# legatus_1_1.net
KiCad netlist of a schematic drawn in EAGLE
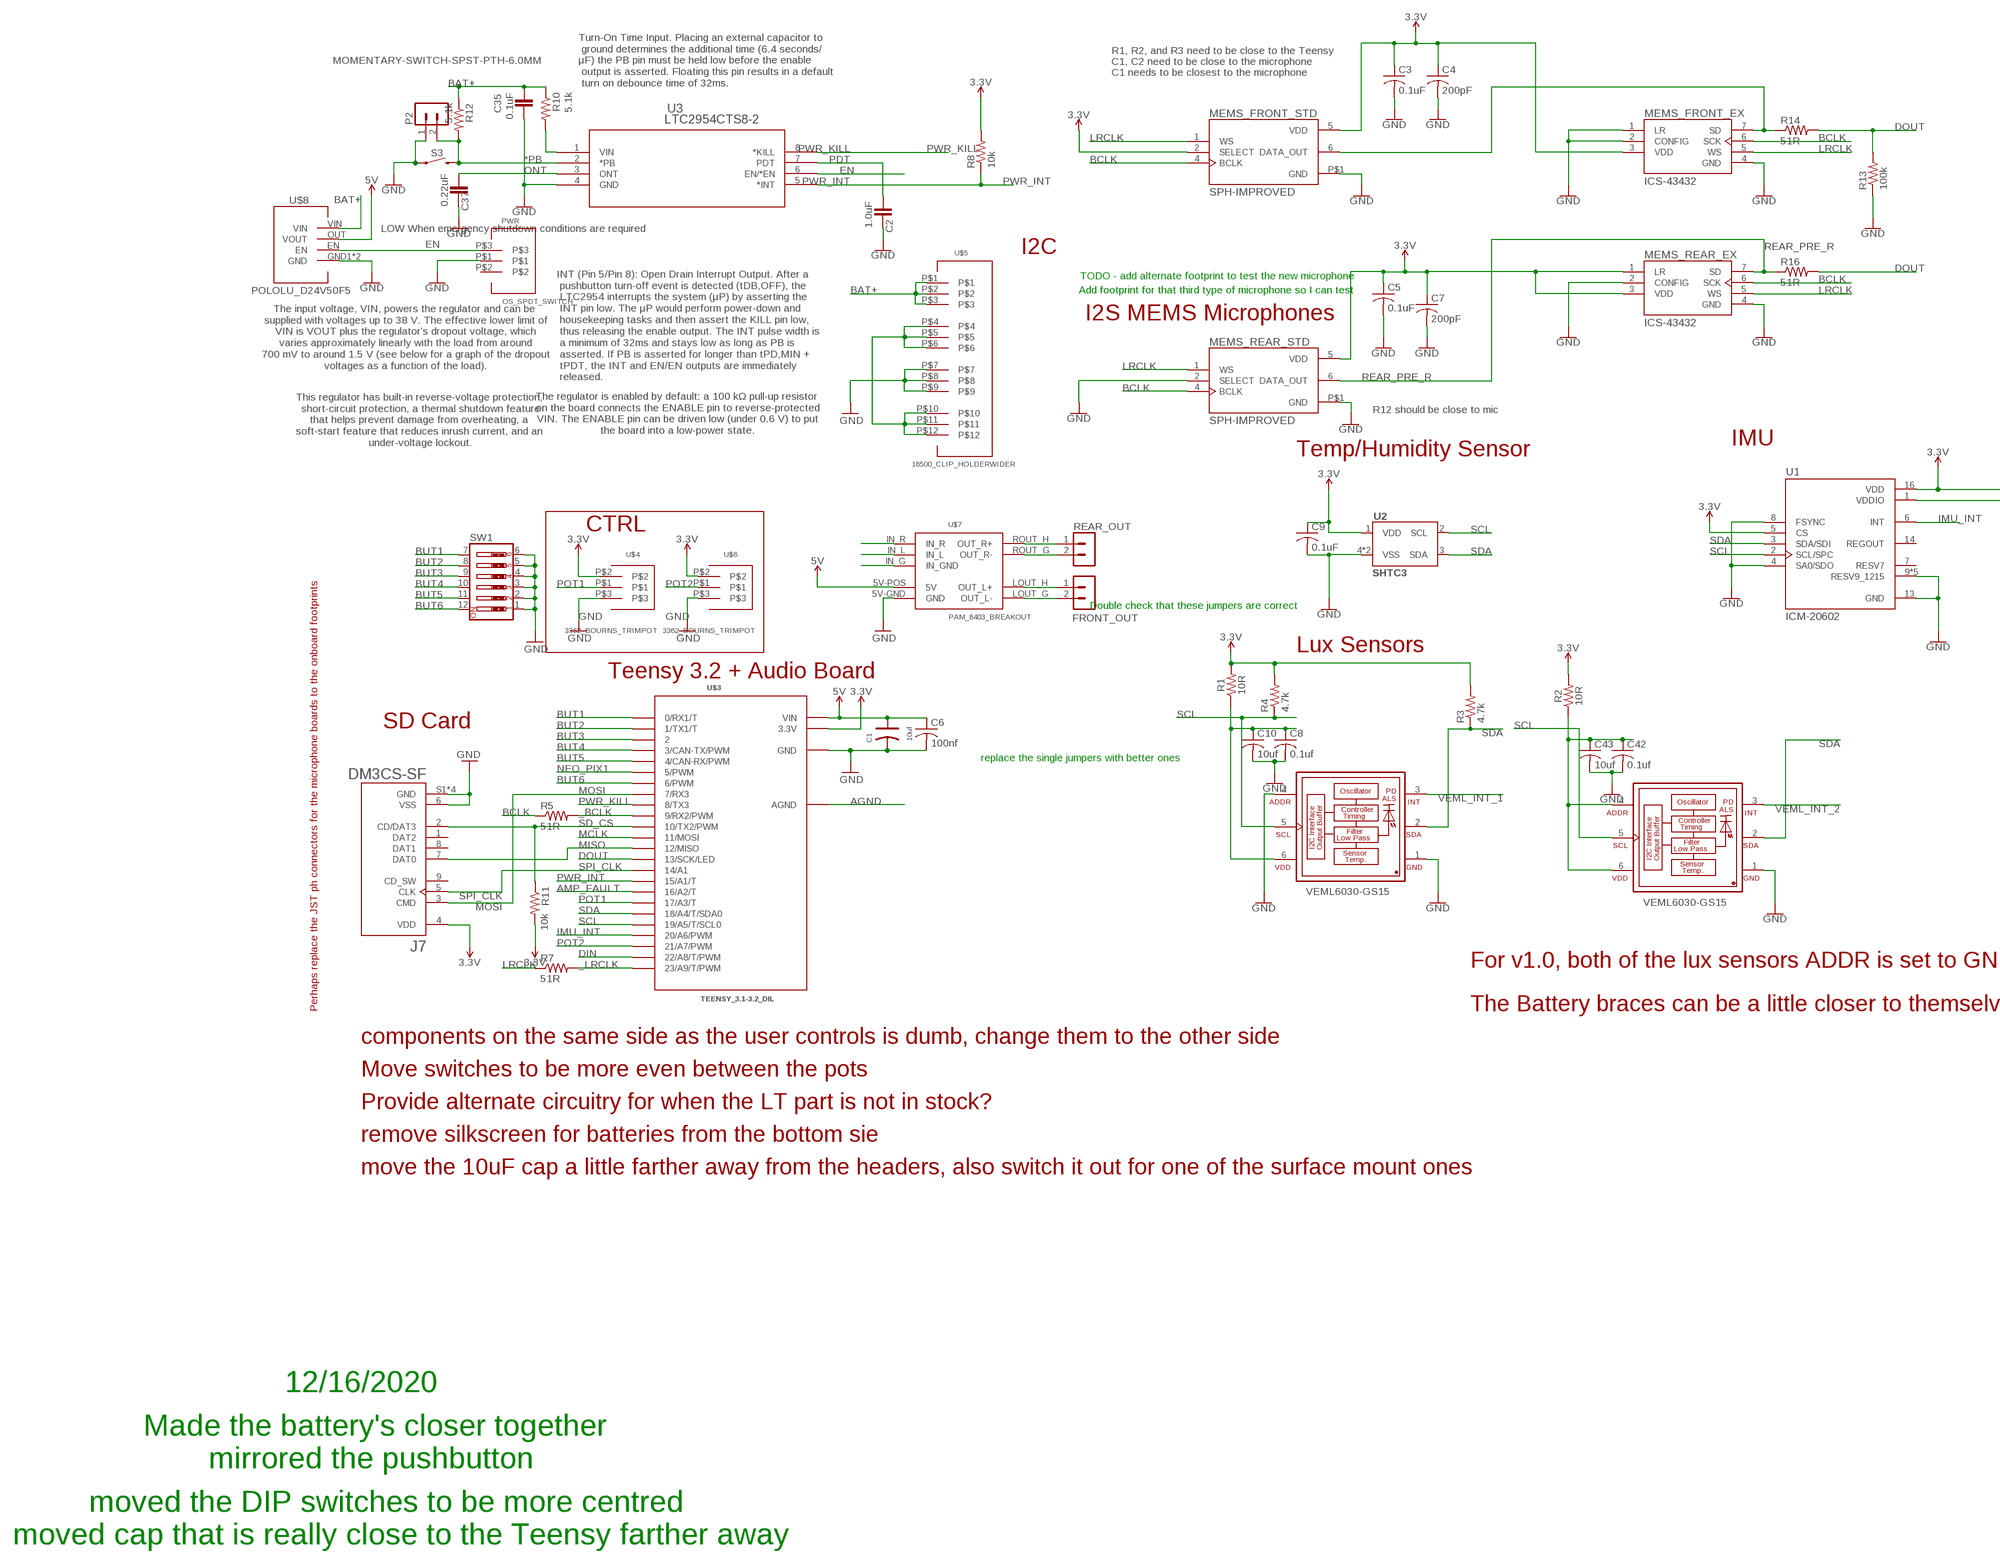
[diagram p0: schematic, sheet 1, part 1 of 2]
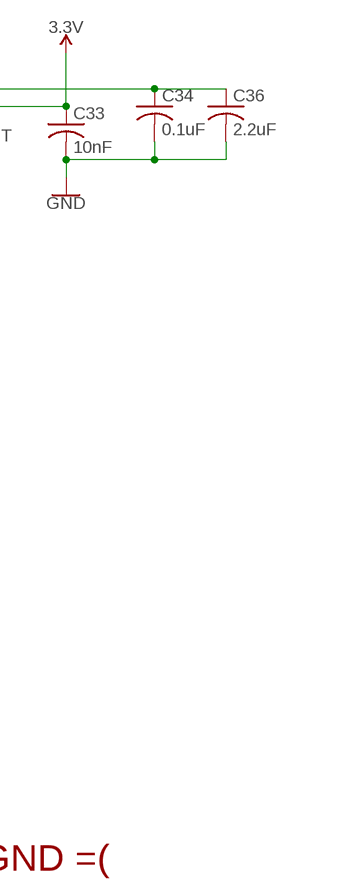
[diagram p1: schematic, sheet 1, part 2 of 2]
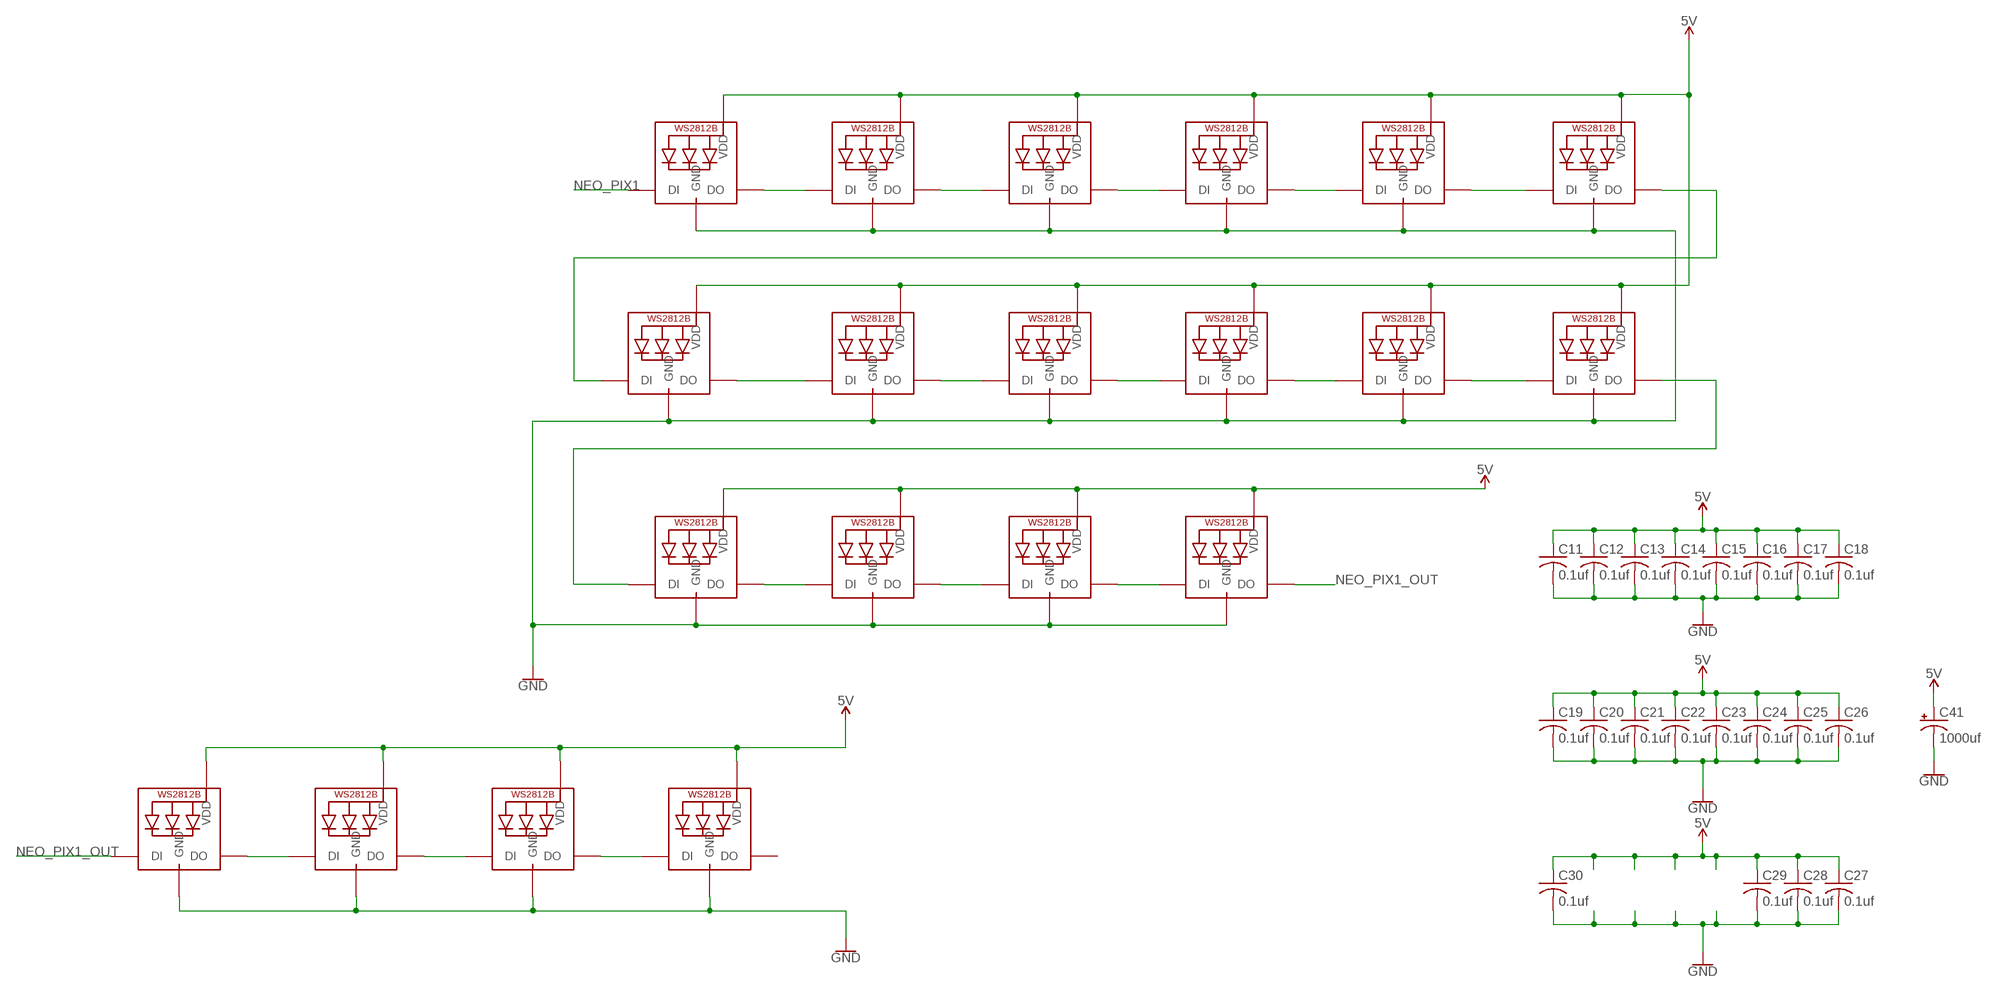
[diagram p2: schematic, sheet 2]

(export (version "E")
  (design (tool "Eeschema 10.0.6"))
  (components
    (comp (ref "C11")
      (value "0.1uf")
      (footprint "eagle-import:C0805")
      (libsource (lib "eagle-import") (part "rcl_334_C-USC0805"))
    )
    (comp (ref "C12")
      (value "0.1uf")
      (footprint "eagle-import:C0805")
      (libsource (lib "eagle-import") (part "rcl_334_C-USC0805"))
    )
    (comp (ref "C13")
      (value "0.1uf")
      (footprint "eagle-import:C0805")
      (libsource (lib "eagle-import") (part "rcl_334_C-USC0805"))
    )
    (comp (ref "C14")
      (value "0.1uf")
      (footprint "eagle-import:C0805")
      (libsource (lib "eagle-import") (part "rcl_334_C-USC0805"))
    )
    (comp (ref "C15")
      (value "0.1uf")
      (footprint "eagle-import:C0805")
      (libsource (lib "eagle-import") (part "rcl_334_C-USC0805"))
    )
    (comp (ref "C16")
      (value "0.1uf")
      (footprint "eagle-import:C0805")
      (libsource (lib "eagle-import") (part "rcl_334_C-USC0805"))
    )
    (comp (ref "C17")
      (value "0.1uf")
      (footprint "eagle-import:C0805")
      (libsource (lib "eagle-import") (part "rcl_334_C-USC0805"))
    )
    (comp (ref "C18")
      (value "0.1uf")
      (footprint "eagle-import:C0805")
      (libsource (lib "eagle-import") (part "rcl_334_C-USC0805"))
    )
    (comp (ref "C19")
      (value "0.1uf")
      (footprint "eagle-import:C0805")
      (libsource (lib "eagle-import") (part "rcl_334_C-USC0805"))
    )
    (comp (ref "C20")
      (value "0.1uf")
      (footprint "eagle-import:C0805")
      (libsource (lib "eagle-import") (part "rcl_334_C-USC0805"))
    )
    (comp (ref "C21")
      (value "0.1uf")
      (footprint "eagle-import:C0805")
      (libsource (lib "eagle-import") (part "rcl_334_C-USC0805"))
    )
    (comp (ref "C22")
      (value "0.1uf")
      (footprint "eagle-import:C0805")
      (libsource (lib "eagle-import") (part "rcl_334_C-USC0805"))
    )
    (comp (ref "C23")
      (value "0.1uf")
      (footprint "eagle-import:C0805")
      (libsource (lib "eagle-import") (part "rcl_334_C-USC0805"))
    )
    (comp (ref "C24")
      (value "0.1uf")
      (footprint "eagle-import:C0805")
      (libsource (lib "eagle-import") (part "rcl_334_C-USC0805"))
    )
    (comp (ref "C25")
      (value "0.1uf")
      (footprint "eagle-import:C0805")
      (libsource (lib "eagle-import") (part "rcl_334_C-USC0805"))
    )
    (comp (ref "C26")
      (value "0.1uf")
      (footprint "eagle-import:C0805")
      (libsource (lib "eagle-import") (part "rcl_334_C-USC0805"))
    )
    (comp (ref "C27")
      (value "0.1uf")
      (footprint "eagle-import:C0805")
      (libsource (lib "eagle-import") (part "rcl_334_C-USC0805"))
    )
    (comp (ref "C28")
      (value "0.1uf")
      (footprint "eagle-import:C0805")
      (libsource (lib "eagle-import") (part "rcl_334_C-USC0805"))
    )
    (comp (ref "C29")
      (value "0.1uf")
      (footprint "eagle-import:C0805")
      (libsource (lib "eagle-import") (part "rcl_334_C-USC0805"))
    )
    (comp (ref "C30")
      (value "0.1uf")
      (footprint "eagle-import:C0805")
      (libsource (lib "eagle-import") (part "rcl_334_C-USC0805"))
    )
    (comp (ref "C41")
      (value "1000uf")
      (footprint "eagle-import:153CLV-1010")
      (libsource (lib "eagle-import") (part "CPOL-US153CLV-1010"))
    )
    (comp (ref "LED1")
      (value "WS2812B_5050N")
      (footprint "eagle-import:WS2812B-NARROW")
      (libsource (lib "eagle-import") (part "WS2812B_5050N"))
    )
    (comp (ref "LED2")
      (value "WS2812B_5050N")
      (footprint "eagle-import:WS2812B-NARROW")
      (libsource (lib "eagle-import") (part "WS2812B_5050N"))
    )
    (comp (ref "LED3")
      (value "WS2812B_5050N")
      (footprint "eagle-import:WS2812B-NARROW")
      (libsource (lib "eagle-import") (part "WS2812B_5050N"))
    )
    (comp (ref "LED4")
      (value "WS2812B_5050N")
      (footprint "eagle-import:WS2812B-NARROW")
      (libsource (lib "eagle-import") (part "WS2812B_5050N"))
    )
    (comp (ref "LED5")
      (value "WS2812B_5050N")
      (footprint "eagle-import:WS2812B-NARROW")
      (libsource (lib "eagle-import") (part "WS2812B_5050N"))
    )
    (comp (ref "LED6")
      (value "WS2812B_5050N")
      (footprint "eagle-import:WS2812B-NARROW")
      (libsource (lib "eagle-import") (part "WS2812B_5050N"))
    )
    (comp (ref "LED7")
      (value "WS2812B_5050N")
      (footprint "eagle-import:WS2812B-NARROW")
      (libsource (lib "eagle-import") (part "WS2812B_5050N"))
    )
    (comp (ref "LED8")
      (value "WS2812B_5050N")
      (footprint "eagle-import:WS2812B-NARROW")
      (libsource (lib "eagle-import") (part "WS2812B_5050N"))
    )
    (comp (ref "LED9")
      (value "WS2812B_5050N")
      (footprint "eagle-import:WS2812B-NARROW")
      (libsource (lib "eagle-import") (part "WS2812B_5050N"))
    )
    (comp (ref "LED10")
      (value "WS2812B_5050N")
      (footprint "eagle-import:WS2812B-NARROW")
      (libsource (lib "eagle-import") (part "WS2812B_5050N"))
    )
    (comp (ref "LED11")
      (value "WS2812B_5050N")
      (footprint "eagle-import:WS2812B-NARROW")
      (libsource (lib "eagle-import") (part "WS2812B_5050N"))
    )
    (comp (ref "LED12")
      (value "WS2812B_5050N")
      (footprint "eagle-import:WS2812B-NARROW")
      (libsource (lib "eagle-import") (part "WS2812B_5050N"))
    )
    (comp (ref "LED13")
      (value "WS2812B_5050N")
      (footprint "eagle-import:WS2812B-NARROW")
      (libsource (lib "eagle-import") (part "WS2812B_5050N"))
    )
    (comp (ref "LED14")
      (value "WS2812B_5050N")
      (footprint "eagle-import:WS2812B-NARROW")
      (libsource (lib "eagle-import") (part "WS2812B_5050N"))
    )
    (comp (ref "LED15")
      (value "WS2812B_5050N")
      (footprint "eagle-import:WS2812B-NARROW")
      (libsource (lib "eagle-import") (part "WS2812B_5050N"))
    )
    (comp (ref "LED16")
      (value "WS2812B_5050N")
      (footprint "eagle-import:WS2812B-NARROW")
      (libsource (lib "eagle-import") (part "WS2812B_5050N"))
    )
    (comp (ref "LED17")
      (value "WS2812B_5050N")
      (footprint "eagle-import:WS2812B-NARROW")
      (libsource (lib "eagle-import") (part "WS2812B_5050N"))
    )
    (comp (ref "LED18")
      (value "WS2812B_5050N")
      (footprint "eagle-import:WS2812B-NARROW")
      (libsource (lib "eagle-import") (part "WS2812B_5050N"))
    )
    (comp (ref "LED19")
      (value "WS2812B_5050N")
      (footprint "eagle-import:WS2812B-NARROW")
      (libsource (lib "eagle-import") (part "WS2812B_5050N"))
    )
    (comp (ref "LED20")
      (value "WS2812B_5050N")
      (footprint "eagle-import:WS2812B-NARROW")
      (libsource (lib "eagle-import") (part "WS2812B_5050N"))
    )
    (comp (ref "C1")
      (value "10uf")
      (footprint "eagle-import:PC-D5.3MM")
      (fields (field (name "MPN") "KS 100uF/16V"))
      (libsource (lib "eagle-import") (part "DIP-ALUMINUM-47UF-16V(D5-H7MM)"))
    )
    (comp (ref "C2")
      (value "1.0uF")
      (footprint "eagle-import:CAPC2012X110")
      (libsource (lib "eagle-import") (part "CCHIP-0805(2012-METRIC)_"))
    )
    (comp (ref "C3")
      (value "0.1uF")
      (footprint "eagle-import:C0805")
      (libsource (lib "eagle-import") (part "rcl_334_C-USC0805"))
    )
    (comp (ref "C4")
      (value "200pF")
      (footprint "eagle-import:C0805")
      (libsource (lib "eagle-import") (part "rcl_334_C-USC0805"))
    )
    (comp (ref "C5")
      (value "0.1uF")
      (footprint "eagle-import:C0805")
      (libsource (lib "eagle-import") (part "rcl_334_C-USC0805"))
    )
    (comp (ref "C6")
      (value "100nf")
      (footprint "eagle-import:C2012")
      (libsource (lib "eagle-import") (part "C-USC2012"))
    )
    (comp (ref "C7")
      (value "200pF")
      (footprint "eagle-import:C0805")
      (libsource (lib "eagle-import") (part "rcl_334_C-USC0805"))
    )
    (comp (ref "C8")
      (value "0.1uf")
      (footprint "eagle-import:C0805")
      (libsource (lib "eagle-import") (part "rcl_334_C-USC0805"))
    )
    (comp (ref "C9")
      (value "0.1uF")
      (footprint "eagle-import:C0805")
      (libsource (lib "eagle-import") (part "rcl_334_C-USC0805"))
    )
    (comp (ref "C10")
      (value "10uf")
      (footprint "eagle-import:C0805")
      (libsource (lib "eagle-import") (part "rcl_334_C-USC0805"))
    )
    (comp (ref "C33")
      (value "10nF")
      (footprint "eagle-import:C0805")
      (libsource (lib "eagle-import") (part "rcl_334_C-USC0805"))
    )
    (comp (ref "C34")
      (value "0.1uF")
      (footprint "eagle-import:C0805")
      (libsource (lib "eagle-import") (part "rcl_334_C-USC0805"))
    )
    (comp (ref "C35")
      (value "0.1uF")
      (footprint "eagle-import:CAPC2012X110")
      (libsource (lib "eagle-import") (part "CCHIP-0805(2012-METRIC)_"))
    )
    (comp (ref "C36")
      (value "2.2uF")
      (footprint "eagle-import:C0805")
      (libsource (lib "eagle-import") (part "rcl_334_C-USC0805"))
    )
    (comp (ref "C37")
      (value "0.22uF")
      (footprint "eagle-import:CAPC2012X110")
      (libsource (lib "eagle-import") (part "CCHIP-0805(2012-METRIC)_"))
    )
    (comp (ref "C42")
      (value "0.1uf")
      (footprint "eagle-import:C0805")
      (libsource (lib "eagle-import") (part "rcl_334_C-USC0805"))
    )
    (comp (ref "C43")
      (value "10uf")
      (footprint "eagle-import:C0805")
      (libsource (lib "eagle-import") (part "rcl_334_C-USC0805"))
    )
    (comp (ref "FRONT_OUT")
      (value "B2B-PH-K")
      (footprint "eagle-import:B2B-PH-K")
      (libsource (lib "eagle-import") (part "B2B-PH-K"))
    )
    (comp (ref "J7")
      (value "DM3CS-SF")
      (footprint "eagle-import:HRS_DM3CS-SF")
      (fields (field (name "MF") "Hirose"))
      (libsource (lib "eagle-import") (part "DM3CS-SF"))
    )
    (comp (ref "MEMS_FRONT_EX")
      (value "ICS-43432")
      (footprint "eagle-import:ICS-43432")
      (fields
        (field (name "DIGIKEY_PARTNO") "1428-1053-2-ND")
        (field (name "MANUFACTURER") "TDK InvenSense")
        (field (name "CREATED_BY") "PCBLayout.com")
      )
      (libsource (lib "eagle-import") (part "ICS-43432"))
    )
    (comp (ref "MEMS_FRONT_STD")
      (value "SPH-IMPROVED")
      (footprint "eagle-import:MIC_SPH0645LM4H-B_LARGER_RING")
      (libsource (lib "eagle-import") (part "SPH-IMPROVED"))
    )
    (comp (ref "MEMS_REAR_EX")
      (value "ICS-43432")
      (footprint "eagle-import:ICS-43432")
      (fields
        (field (name "DIGIKEY_PARTNO") "1428-1053-2-ND")
        (field (name "MANUFACTURER") "TDK InvenSense")
        (field (name "CREATED_BY") "PCBLayout.com")
      )
      (libsource (lib "eagle-import") (part "ICS-43432"))
    )
    (comp (ref "MEMS_REAR_STD")
      (value "SPH-IMPROVED")
      (footprint "eagle-import:MIC_SPH0645LM4H-B_LARGER_RING")
      (libsource (lib "eagle-import") (part "SPH-IMPROVED"))
    )
    (comp (ref "P2")
      (value "B2B-PH-K")
      (footprint "eagle-import:B2B-PH-K")
      (libsource (lib "eagle-import") (part "B2B-PH-K"))
    )
    (comp (ref "PWR")
      (value "OS_SPDT_SWITCH")
      (footprint "eagle-import:OS_SPDT_SLIDE_SWITCH")
      (libsource (lib "eagle-import") (part "OS_SPDT_SWITCH"))
    )
    (comp (ref "R1")
      (value "10R")
      (footprint "eagle-import:R0805")
      (libsource (lib "eagle-import") (part "audio amplifier example_970892_R-US_R0805"))
    )
    (comp (ref "R2")
      (value "10R")
      (footprint "eagle-import:R0805")
      (libsource (lib "eagle-import") (part "audio amplifier example_970892_R-US_R0805"))
    )
    (comp (ref "R3")
      (value "4.7k")
      (footprint "eagle-import:M0805")
      (libsource (lib "eagle-import") (part "adafruit_420_R-US_M0805"))
    )
    (comp (ref "R4")
      (value "4.7k")
      (footprint "eagle-import:M0805")
      (libsource (lib "eagle-import") (part "adafruit_420_R-US_M0805"))
    )
    (comp (ref "R5")
      (value "51R")
      (footprint "eagle-import:M0805")
      (libsource (lib "eagle-import") (part "adafruit_420_R-US_M0805"))
    )
    (comp (ref "R7")
      (value "51R")
      (footprint "eagle-import:M0805")
      (libsource (lib "eagle-import") (part "adafruit_420_R-US_M0805"))
    )
    (comp (ref "R8")
      (value "10k")
      (footprint "eagle-import:R0805")
      (libsource (lib "eagle-import") (part "R-US_R0805"))
    )
    (comp (ref "R10")
      (value "5.1k")
      (footprint "eagle-import:R0805")
      (libsource (lib "eagle-import") (part "R-US_R0805"))
    )
    (comp (ref "R11")
      (value "10k")
      (footprint "eagle-import:M0805")
      (libsource (lib "eagle-import") (part "rcl_R-US_M0805"))
    )
    (comp (ref "R12")
      (value "5.1k")
      (footprint "eagle-import:R0805")
      (libsource (lib "eagle-import") (part "R-US_R0805"))
    )
    (comp (ref "R13")
      (value "100k")
      (footprint "eagle-import:M0805")
      (libsource (lib "eagle-import") (part "adafruit_420_R-US_M0805"))
    )
    (comp (ref "R14")
      (value "51R")
      (footprint "eagle-import:M0805")
      (libsource (lib "eagle-import") (part "adafruit_420_R-US_M0805"))
    )
    (comp (ref "R16")
      (value "51R")
      (footprint "eagle-import:M0805")
      (libsource (lib "eagle-import") (part "adafruit_420_R-US_M0805"))
    )
    (comp (ref "REAR_OUT")
      (value "B2B-PH-K")
      (footprint "eagle-import:B2B-PH-K")
      (libsource (lib "eagle-import") (part "B2B-PH-K"))
    )
    (comp (ref "S3")
      (value "MOMENTARY-SWITCH-SPST-PTH-6.0MM")
      (footprint "eagle-import:TACTILE_SWITCH_PTH_6.0MM")
      (libsource (lib "eagle-import") (part "MOMENTARY-SWITCH-SPST-PTH-6.0MM"))
    )
    (comp (ref "SW1")
      (value "SW_DIP-6")
      (footprint "eagle-import:EDG-06")
      (libsource (lib "eagle-import") (part "SW_DIP-6"))
    )
    (comp (ref "U$3")
      (value "TEENSY_3.1-3.2_DIL")
      (footprint "eagle-import:TEENSY_3.0-3.2&LC_DIL")
      (libsource (lib "eagle-import") (part "TEENSY_3.1-3.2_DIL"))
    )
    (comp (ref "U$4")
      (value "3362_BOURNS_TRIMPOT")
      (footprint "eagle-import:3362_BOURNS_TRIMPOT")
      (libsource (lib "eagle-import") (part "3362_BOURNS_TRIMPOT"))
    )
    (comp (ref "U$5")
      (value "18500_CLIP_HOLDERWIDER")
      (footprint "eagle-import:3PINBATTERY_CLIP_WIDER")
      (libsource (lib "eagle-import") (part "18500_CLIP_HOLDERWIDER"))
    )
    (comp (ref "U$6")
      (value "3362_BOURNS_TRIMPOT")
      (footprint "eagle-import:3362_BOURNS_TRIMPOT")
      (libsource (lib "eagle-import") (part "3362_BOURNS_TRIMPOT"))
    )
    (comp (ref "U$7")
      (value "PAM_8403_BREAKOUT")
      (footprint "eagle-import:PAM8403_BREAKOUT")
      (libsource (lib "eagle-import") (part "PAM_8403_BREAKOUT"))
    )
    (comp (ref "U$8")
      (value "POLOLU_D24V50F5")
      (footprint "eagle-import:POLOLU_D24V50F5")
      (libsource (lib "eagle-import") (part "POLOLU_D24V50F5"))
    )
    (comp (ref "U1")
      (value "ICM-20602")
      (footprint "eagle-import:PQFN50P300X300X80-16N")
      (fields (field (name "MF") "TDK InvenSense"))
      (libsource (lib "eagle-import") (part "ICM-20602"))
    )
    (comp (ref "U2")
      (value "SHTC3")
      (footprint "eagle-import:SHTC3")
      (libsource (lib "eagle-import") (part "SHTC3"))
    )
    (comp (ref "U3")
      (value "LTC2954CTS8-2")
      (footprint "eagle-import:TSOT-23_TS8")
      (fields (field (name "MF") "Analog Devices / Linear Technology"))
      (libsource (lib "eagle-import") (part "LTC2954CTS8-2"))
    )
    (comp (ref "VMEL_FRONT")
      (value "VEML6030-GS15")
      (footprint "eagle-import:VISHAY_VEML6030_2X2X0.87")
      (fields (field (name "MF") "Vishay Semiconductor"))
      (libsource (lib "eagle-import") (part "VEML6030-GS15"))
    )
    (comp (ref "VMEL_REAR")
      (value "VEML6030-GS15")
      (footprint "eagle-import:VISHAY_VEML6030_2X2X0.87")
      (fields (field (name "MF") "Vishay Semiconductor"))
      (libsource (lib "eagle-import") (part "VEML6030-GS15"))
    )
  )
  (nets
    (net (code "1") (name "*PB") (class "Default")
      (node (ref "P2") (pin "2") (pinfunction "2_2") (pintype "passive"))
      (node (ref "R12") (pin "2") (pinfunction "2_2") (pintype "passive"))
      (node (ref "S3") (pin "3") (pinfunction "2_3") (pintype "passive"))
      (node (ref "U3") (pin "2") (pinfunction "*PB_2") (pintype "input"))
    )
    (net (code "2") (name "3.3V") (class "Default")
      (node (ref "C3") (pin "1") (pinfunction "1_1") (pintype "passive"))
      (node (ref "C33") (pin "1") (pinfunction "1_1") (pintype "passive"))
      (node (ref "C34") (pin "1") (pinfunction "1_1") (pintype "passive"))
      (node (ref "C36") (pin "1") (pinfunction "1_1") (pintype "passive"))
      (node (ref "C4") (pin "1") (pinfunction "1_1") (pintype "passive"))
      (node (ref "C5") (pin "1") (pinfunction "1_1") (pintype "passive"))
      (node (ref "C7") (pin "1") (pinfunction "1_1") (pintype "passive"))
      (node (ref "C9") (pin "1") (pinfunction "1_1") (pintype "passive"))
      (node (ref "J7") (pin "4") (pinfunction "VDD_4") (pintype "passive"))
      (node (ref "MEMS_FRONT_EX") (pin "3") (pinfunction "VDD_3") (pintype "power_in"))
      (node (ref "MEMS_FRONT_STD") (pin "2") (pinfunction "SELECT_2") (pintype "input"))
      (node (ref "MEMS_FRONT_STD") (pin "5") (pinfunction "VDD_5") (pintype "power_in"))
      (node (ref "MEMS_REAR_EX") (pin "1") (pinfunction "LR_1") (pintype "input"))
      (node (ref "MEMS_REAR_EX") (pin "3") (pinfunction "VDD_3") (pintype "power_in"))
      (node (ref "MEMS_REAR_STD") (pin "5") (pinfunction "VDD_5") (pintype "power_in"))
      (node (ref "R1") (pin "2") (pinfunction "2_2") (pintype "passive"))
      (node (ref "R11") (pin "2") (pinfunction "2_2") (pintype "passive"))
      (node (ref "R2") (pin "2") (pinfunction "2_2") (pintype "passive"))
      (node (ref "R3") (pin "2") (pinfunction "2_2") (pintype "passive"))
      (node (ref "R4") (pin "2") (pinfunction "2_2") (pintype "passive"))
      (node (ref "R8") (pin "2") (pinfunction "2_2") (pintype "passive"))
      (node (ref "U$3") (pin "3.3V") (pinfunction "3.3V_3.3V") (pintype "power_in"))
      (node (ref "U$4") (pin "P$2") (pinfunction "P$2_P$2") (pintype "bidirectional"))
      (node (ref "U$6") (pin "P$2") (pinfunction "P$2_P$2") (pintype "bidirectional"))
      (node (ref "U1") (pin "1") (pinfunction "VDDIO_1") (pintype "power_in"))
      (node (ref "U1") (pin "16") (pinfunction "VDD_16") (pintype "power_in"))
      (node (ref "U1") (pin "5") (pinfunction "CS_5") (pintype "input"))
      (node (ref "U2") (pin "1") (pinfunction "VDD_1") (pintype "bidirectional"))
    )
    (net (code "3") (name "5V") (class "Default")
      (node (ref "C1") (pin "+") (pinfunction "+_+") (pintype "passive"))
      (node (ref "C11") (pin "1") (pinfunction "1_1") (pintype "passive"))
      (node (ref "C12") (pin "1") (pinfunction "1_1") (pintype "passive"))
      (node (ref "C13") (pin "1") (pinfunction "1_1") (pintype "passive"))
      (node (ref "C14") (pin "1") (pinfunction "1_1") (pintype "passive"))
      (node (ref "C15") (pin "1") (pinfunction "1_1") (pintype "passive"))
      (node (ref "C16") (pin "1") (pinfunction "1_1") (pintype "passive"))
      (node (ref "C17") (pin "1") (pinfunction "1_1") (pintype "passive"))
      (node (ref "C18") (pin "1") (pinfunction "1_1") (pintype "passive"))
      (node (ref "C19") (pin "1") (pinfunction "1_1") (pintype "passive"))
      (node (ref "C20") (pin "1") (pinfunction "1_1") (pintype "passive"))
      (node (ref "C21") (pin "1") (pinfunction "1_1") (pintype "passive"))
      (node (ref "C22") (pin "1") (pinfunction "1_1") (pintype "passive"))
      (node (ref "C23") (pin "1") (pinfunction "1_1") (pintype "passive"))
      (node (ref "C24") (pin "1") (pinfunction "1_1") (pintype "passive"))
      (node (ref "C25") (pin "1") (pinfunction "1_1") (pintype "passive"))
      (node (ref "C26") (pin "1") (pinfunction "1_1") (pintype "passive"))
      (node (ref "C27") (pin "1") (pinfunction "1_1") (pintype "passive"))
      (node (ref "C28") (pin "1") (pinfunction "1_1") (pintype "passive"))
      (node (ref "C29") (pin "1") (pinfunction "1_1") (pintype "passive"))
      (node (ref "C30") (pin "1") (pinfunction "1_1") (pintype "passive"))
      (node (ref "C41") (pin "+") (pinfunction "+_+") (pintype "passive"))
      (node (ref "C6") (pin "1") (pinfunction "1_1") (pintype "passive"))
      (node (ref "LED1") (pin "1-VDD") (pinfunction "VDD_1-VDD") (pintype "power_in"))
      (node (ref "LED10") (pin "1-VDD") (pinfunction "VDD_1-VDD") (pintype "power_in"))
      (node (ref "LED11") (pin "1-VDD") (pinfunction "VDD_1-VDD") (pintype "power_in"))
      (node (ref "LED12") (pin "1-VDD") (pinfunction "VDD_1-VDD") (pintype "power_in"))
      (node (ref "LED13") (pin "1-VDD") (pinfunction "VDD_1-VDD") (pintype "power_in"))
      (node (ref "LED14") (pin "1-VDD") (pinfunction "VDD_1-VDD") (pintype "power_in"))
      (node (ref "LED15") (pin "1-VDD") (pinfunction "VDD_1-VDD") (pintype "power_in"))
      (node (ref "LED16") (pin "1-VDD") (pinfunction "VDD_1-VDD") (pintype "power_in"))
      (node (ref "LED17") (pin "1-VDD") (pinfunction "VDD_1-VDD") (pintype "power_in"))
      (node (ref "LED18") (pin "1-VDD") (pinfunction "VDD_1-VDD") (pintype "power_in"))
      (node (ref "LED19") (pin "1-VDD") (pinfunction "VDD_1-VDD") (pintype "power_in"))
      (node (ref "LED2") (pin "1-VDD") (pinfunction "VDD_1-VDD") (pintype "power_in"))
      (node (ref "LED20") (pin "1-VDD") (pinfunction "VDD_1-VDD") (pintype "power_in"))
      (node (ref "LED3") (pin "1-VDD") (pinfunction "VDD_1-VDD") (pintype "power_in"))
      (node (ref "LED4") (pin "1-VDD") (pinfunction "VDD_1-VDD") (pintype "power_in"))
      (node (ref "LED5") (pin "1-VDD") (pinfunction "VDD_1-VDD") (pintype "power_in"))
      (node (ref "LED6") (pin "1-VDD") (pinfunction "VDD_1-VDD") (pintype "power_in"))
      (node (ref "LED7") (pin "1-VDD") (pinfunction "VDD_1-VDD") (pintype "power_in"))
      (node (ref "LED8") (pin "1-VDD") (pinfunction "VDD_1-VDD") (pintype "power_in"))
      (node (ref "LED9") (pin "1-VDD") (pinfunction "VDD_1-VDD") (pintype "power_in"))
      (node (ref "U$3") (pin "VIN") (pinfunction "VIN_VIN") (pintype "power_in"))
      (node (ref "U$7") (pin "5V-POS") (pinfunction "5V_5V-POS") (pintype "bidirectional"))
      (node (ref "U$8") (pin "OUT") (pinfunction "VOUT_OUT") (pintype "bidirectional"))
    )
    (net (code "4") (name "AGND") (class "Default")
      (node (ref "U$3") (pin "AGND") (pinfunction "AGND_AGND") (pintype "power_in"))
    )
    (net (code "5") (name "AMP_FAULT") (class "Default")
      (node (ref "U$3") (pin "16/A2") (pinfunction "16/A2/T_16/A2") (pintype "bidirectional"))
    )
    (net (code "6") (name "BAT+") (class "Default")
      (node (ref "C35") (pin "1") (pinfunction "1_1") (pintype "passive"))
      (node (ref "R10") (pin "1") (pinfunction "1_1") (pintype "passive"))
      (node (ref "R12") (pin "1") (pinfunction "1_1") (pintype "passive"))
      (node (ref "U$5") (pin "P$1") (pinfunction "P$1_P$1") (pintype "bidirectional"))
      (node (ref "U$5") (pin "P$2") (pinfunction "P$2_P$2") (pintype "bidirectional"))
      (node (ref "U$5") (pin "P$3") (pinfunction "P$3_P$3") (pintype "bidirectional"))
      (node (ref "U$8") (pin "VIN") (pinfunction "VIN_VIN") (pintype "bidirectional"))
    )
    (net (code "7") (name "BCLK") (class "Default")
      (node (ref "MEMS_FRONT_EX") (pin "6") (pinfunction "SCK_6") (pintype "input"))
      (node (ref "MEMS_FRONT_STD") (pin "4") (pinfunction "BCLK_4") (pintype "input"))
      (node (ref "MEMS_REAR_EX") (pin "6") (pinfunction "SCK_6") (pintype "input"))
      (node (ref "MEMS_REAR_STD") (pin "4") (pinfunction "BCLK_4") (pintype "input"))
      (node (ref "R5") (pin "1") (pinfunction "1_1") (pintype "passive"))
    )
    (net (code "8") (name "BUT1") (class "Default")
      (node (ref "SW1") (pin "7") (pinfunction "7_7") (pintype "passive"))
      (node (ref "U$3") (pin "0") (pinfunction "0/RX1/T_0") (pintype "bidirectional"))
    )
    (net (code "9") (name "BUT2") (class "Default")
      (node (ref "SW1") (pin "8") (pinfunction "8_8") (pintype "passive"))
      (node (ref "U$3") (pin "1") (pinfunction "1/TX1/T_1") (pintype "bidirectional"))
    )
    (net (code "10") (name "BUT3") (class "Default")
      (node (ref "SW1") (pin "9") (pinfunction "9_9") (pintype "passive"))
      (node (ref "U$3") (pin "2") (pinfunction "2_2") (pintype "bidirectional"))
    )
    (net (code "11") (name "BUT4") (class "Default")
      (node (ref "SW1") (pin "10") (pinfunction "10_10") (pintype "passive"))
      (node (ref "U$3") (pin "3") (pinfunction "3/CAN-TX/PWM_3") (pintype "bidirectional"))
    )
    (net (code "12") (name "BUT5") (class "Default")
      (node (ref "SW1") (pin "11") (pinfunction "11_11") (pintype "passive"))
      (node (ref "U$3") (pin "4") (pinfunction "4/CAN-RX/PWM_4") (pintype "bidirectional"))
    )
    (net (code "13") (name "BUT6") (class "Default")
      (node (ref "SW1") (pin "12") (pinfunction "12_12") (pintype "passive"))
      (node (ref "U$3") (pin "6") (pinfunction "6/PWM_6") (pintype "bidirectional"))
    )
    (net (code "14") (name "DIN") (class "Default")
      (node (ref "U$3") (pin "22/A8") (pinfunction "22/A8/T/PWM_22/A8") (pintype "bidirectional"))
    )
    (net (code "15") (name "DOUT") (class "Default")
      (node (ref "R13") (pin "2") (pinfunction "2_2") (pintype "passive"))
      (node (ref "R14") (pin "2") (pinfunction "2_2") (pintype "passive"))
      (node (ref "R16") (pin "2") (pinfunction "2_2") (pintype "passive"))
      (node (ref "U$3") (pin "13") (pinfunction "13/SCK/LED_13") (pintype "bidirectional"))
    )
    (net (code "16") (name "EN") (class "Default")
      (node (ref "PWR") (pin "P$3") (pinfunction "P$3_P$3") (pintype "bidirectional"))
      (node (ref "U$8") (pin "EN") (pinfunction "EN_EN") (pintype "bidirectional"))
      (node (ref "U3") (pin "6") (pinfunction "EN/*EN_6") (pintype "output"))
    )
    (net (code "17") (name "GND") (class "Default")
      (node (ref "C1") (pin "-") (pinfunction "-_-") (pintype "passive"))
      (node (ref "C10") (pin "2") (pinfunction "2_2") (pintype "passive"))
      (node (ref "C11") (pin "2") (pinfunction "2_2") (pintype "passive"))
      (node (ref "C12") (pin "2") (pinfunction "2_2") (pintype "passive"))
      (node (ref "C13") (pin "2") (pinfunction "2_2") (pintype "passive"))
      (node (ref "C14") (pin "2") (pinfunction "2_2") (pintype "passive"))
      (node (ref "C15") (pin "2") (pinfunction "2_2") (pintype "passive"))
      (node (ref "C16") (pin "2") (pinfunction "2_2") (pintype "passive"))
      (node (ref "C17") (pin "2") (pinfunction "2_2") (pintype "passive"))
      (node (ref "C18") (pin "2") (pinfunction "2_2") (pintype "passive"))
      (node (ref "C19") (pin "2") (pinfunction "2_2") (pintype "passive"))
      (node (ref "C2") (pin "2") (pinfunction "2_2") (pintype "passive"))
      (node (ref "C20") (pin "2") (pinfunction "2_2") (pintype "passive"))
      (node (ref "C21") (pin "2") (pinfunction "2_2") (pintype "passive"))
      (node (ref "C22") (pin "2") (pinfunction "2_2") (pintype "passive"))
      (node (ref "C23") (pin "2") (pinfunction "2_2") (pintype "passive"))
      (node (ref "C24") (pin "2") (pinfunction "2_2") (pintype "passive"))
      (node (ref "C25") (pin "2") (pinfunction "2_2") (pintype "passive"))
      (node (ref "C26") (pin "2") (pinfunction "2_2") (pintype "passive"))
      (node (ref "C27") (pin "2") (pinfunction "2_2") (pintype "passive"))
      (node (ref "C28") (pin "2") (pinfunction "2_2") (pintype "passive"))
      (node (ref "C29") (pin "2") (pinfunction "2_2") (pintype "passive"))
      (node (ref "C3") (pin "2") (pinfunction "2_2") (pintype "passive"))
      (node (ref "C30") (pin "2") (pinfunction "2_2") (pintype "passive"))
      (node (ref "C33") (pin "2") (pinfunction "2_2") (pintype "passive"))
      (node (ref "C34") (pin "2") (pinfunction "2_2") (pintype "passive"))
      (node (ref "C35") (pin "2") (pinfunction "2_2") (pintype "passive"))
      (node (ref "C36") (pin "2") (pinfunction "2_2") (pintype "passive"))
      (node (ref "C37") (pin "2") (pinfunction "2_2") (pintype "passive"))
      (node (ref "C4") (pin "2") (pinfunction "2_2") (pintype "passive"))
      (node (ref "C41") (pin "-") (pinfunction "-_-") (pintype "passive"))
      (node (ref "C42") (pin "2") (pinfunction "2_2") (pintype "passive"))
      (node (ref "C43") (pin "2") (pinfunction "2_2") (pintype "passive"))
      (node (ref "C5") (pin "2") (pinfunction "2_2") (pintype "passive"))
      (node (ref "C6") (pin "2") (pinfunction "2_2") (pintype "passive"))
      (node (ref "C7") (pin "2") (pinfunction "2_2") (pintype "passive"))
      (node (ref "C8") (pin "2") (pinfunction "2_2") (pintype "passive"))
      (node (ref "C9") (pin "2") (pinfunction "2_2") (pintype "passive"))
      (node (ref "J7") (pin "6") (pinfunction "VSS_6") (pintype "passive"))
      (node (ref "J7") (pin "S1") (pinfunction "GND_S1") (pintype "passive"))
      (node (ref "J7") (pin "S2") (pinfunction "GND_S2") (pintype "passive"))
      (node (ref "J7") (pin "S3") (pinfunction "GND_S3") (pintype "passive"))
      (node (ref "J7") (pin "S5") (pinfunction "GND_S5") (pintype "passive"))
      (node (ref "LED1") (pin "3-GND") (pinfunction "GND_3-GND") (pintype "power_in"))
      (node (ref "LED10") (pin "3-GND") (pinfunction "GND_3-GND") (pintype "power_in"))
      (node (ref "LED11") (pin "3-GND") (pinfunction "GND_3-GND") (pintype "power_in"))
      (node (ref "LED12") (pin "3-GND") (pinfunction "GND_3-GND") (pintype "power_in"))
      (node (ref "LED13") (pin "3-GND") (pinfunction "GND_3-GND") (pintype "power_in"))
      (node (ref "LED14") (pin "3-GND") (pinfunction "GND_3-GND") (pintype "power_in"))
      (node (ref "LED15") (pin "3-GND") (pinfunction "GND_3-GND") (pintype "power_in"))
      (node (ref "LED16") (pin "3-GND") (pinfunction "GND_3-GND") (pintype "power_in"))
      (node (ref "LED17") (pin "3-GND") (pinfunction "GND_3-GND") (pintype "power_in"))
      (node (ref "LED18") (pin "3-GND") (pinfunction "GND_3-GND") (pintype "power_in"))
      (node (ref "LED19") (pin "3-GND") (pinfunction "GND_3-GND") (pintype "power_in"))
      (node (ref "LED2") (pin "3-GND") (pinfunction "GND_3-GND") (pintype "power_in"))
      (node (ref "LED20") (pin "3-GND") (pinfunction "GND_3-GND") (pintype "power_in"))
      (node (ref "LED3") (pin "3-GND") (pinfunction "GND_3-GND") (pintype "power_in"))
      (node (ref "LED4") (pin "3-GND") (pinfunction "GND_3-GND") (pintype "power_in"))
      (node (ref "LED5") (pin "3-GND") (pinfunction "GND_3-GND") (pintype "power_in"))
      (node (ref "LED6") (pin "3-GND") (pinfunction "GND_3-GND") (pintype "power_in"))
      (node (ref "LED7") (pin "3-GND") (pinfunction "GND_3-GND") (pintype "power_in"))
      (node (ref "LED8") (pin "3-GND") (pinfunction "GND_3-GND") (pintype "power_in"))
      (node (ref "LED9") (pin "3-GND") (pinfunction "GND_3-GND") (pintype "power_in"))
      (node (ref "MEMS_FRONT_EX") (pin "1") (pinfunction "LR_1") (pintype "input"))
      (node (ref "MEMS_FRONT_EX") (pin "2") (pinfunction "CONFIG_2") (pintype "input"))
      (node (ref "MEMS_FRONT_EX") (pin "4") (pinfunction "GND_4") (pintype "power_in"))
      (node (ref "MEMS_FRONT_STD") (pin "P$1") (pinfunction "GND_P$1") (pintype "power_in"))
      (node (ref "MEMS_REAR_EX") (pin "2") (pinfunction "CONFIG_2") (pintype "input"))
      (node (ref "MEMS_REAR_EX") (pin "4") (pinfunction "GND_4") (pintype "power_in"))
      (node (ref "MEMS_REAR_STD") (pin "2") (pinfunction "SELECT_2") (pintype "input"))
      (node (ref "MEMS_REAR_STD") (pin "P$1") (pinfunction "GND_P$1") (pintype "power_in"))
      (node (ref "P2") (pin "1") (pinfunction "1_1") (pintype "passive"))
      (node (ref "PWR") (pin "P$1") (pinfunction "P$1_P$1") (pintype "bidirectional"))
      (node (ref "R13") (pin "1") (pinfunction "1_1") (pintype "passive"))
      (node (ref "S3") (pin "1") (pinfunction "1_1") (pintype "passive"))
      (node (ref "SW1") (pin "1") (pinfunction "1_1") (pintype "passive"))
      (node (ref "SW1") (pin "2") (pinfunction "2_2") (pintype "passive"))
      (node (ref "SW1") (pin "3") (pinfunction "3_3") (pintype "passive"))
      (node (ref "SW1") (pin "4") (pinfunction "4_4") (pintype "passive"))
      (node (ref "SW1") (pin "5") (pinfunction "5_5") (pintype "passive"))
      (node (ref "SW1") (pin "6") (pinfunction "6_6") (pintype "passive"))
      (node (ref "U$3") (pin "GND") (pinfunction "GND_GND") (pintype "power_in"))
      (node (ref "U$4") (pin "P$3") (pinfunction "P$3_P$3") (pintype "bidirectional"))
      (node (ref "U$5") (pin "P$7") (pinfunction "P$7_P$7") (pintype "bidirectional"))
      (node (ref "U$5") (pin "P$8") (pinfunction "P$8_P$8") (pintype "bidirectional"))
      (node (ref "U$5") (pin "P$9") (pinfunction "P$9_P$9") (pintype "bidirectional"))
      (node (ref "U$6") (pin "P$3") (pinfunction "P$3_P$3") (pintype "bidirectional"))
      (node (ref "U$7") (pin "5V-GND") (pinfunction "GND_5V-GND") (pintype "bidirectional"))
      (node (ref "U$8") (pin "GND1") (pinfunction "GND_GND1") (pintype "bidirectional"))
      (node (ref "U$8") (pin "GND2") (pinfunction "GND_GND2") (pintype "bidirectional"))
      (node (ref "U1") (pin "10") (pinfunction "RESV9_1215_10") (pintype "passive"))
      (node (ref "U1") (pin "11") (pinfunction "RESV9_1215_11") (pintype "passive"))
      (node (ref "U1") (pin "12") (pinfunction "RESV9_1215_12") (pintype "passive"))
      (node (ref "U1") (pin "13") (pinfunction "GND_13") (pintype "power_in"))
      (node (ref "U1") (pin "15") (pinfunction "RESV9_1215_15") (pintype "passive"))
      (node (ref "U1") (pin "4") (pinfunction "SA0/SDO_4") (pintype "output"))
      (node (ref "U1") (pin "8") (pinfunction "FSYNC_8") (pintype "input"))
      (node (ref "U1") (pin "9") (pinfunction "RESV9_1215_9") (pintype "passive"))
      (node (ref "U2") (pin "4") (pinfunction "VSS_4") (pintype "bidirectional"))
      (node (ref "U2") (pin "5") (pinfunction "VSS_5") (pintype "bidirectional"))
      (node (ref "U3") (pin "4") (pinfunction "GND_4") (pintype "power_in"))
      (node (ref "VMEL_FRONT") (pin "1") (pinfunction "GND_1") (pintype "power_in"))
      (node (ref "VMEL_FRONT") (pin "4") (pinfunction "ADDR_4") (pintype "bidirectional"))
      (node (ref "VMEL_REAR") (pin "1") (pinfunction "GND_1") (pintype "power_in"))
    )
    (net (code "18") (name "IMU_INT") (class "Default")
      (node (ref "U$3") (pin "20/A6") (pinfunction "20/A6/PWM_20/A6") (pintype "bidirectional"))
      (node (ref "U1") (pin "6") (pinfunction "INT_6") (pintype "output"))
    )
    (net (code "19") (name "LRCLK") (class "Default")
      (node (ref "MEMS_FRONT_EX") (pin "5") (pinfunction "WS_5") (pintype "input"))
      (node (ref "MEMS_FRONT_STD") (pin "1") (pinfunction "WS_1") (pintype "input"))
      (node (ref "MEMS_REAR_EX") (pin "5") (pinfunction "WS_5") (pintype "input"))
      (node (ref "MEMS_REAR_STD") (pin "1") (pinfunction "WS_1") (pintype "input"))
      (node (ref "R7") (pin "1") (pinfunction "1_1") (pintype "passive"))
    )
    (net (code "20") (name "MCLK") (class "Default")
      (node (ref "U$3") (pin "11") (pinfunction "11/MOSI_11") (pintype "bidirectional"))
    )
    (net (code "21") (name "MISO") (class "Default")
      (node (ref "J7") (pin "7") (pinfunction "DAT0_7") (pintype "passive"))
      (node (ref "U$3") (pin "12") (pinfunction "12/MISO_12") (pintype "bidirectional"))
    )
    (net (code "22") (name "MOSI") (class "Default")
      (node (ref "J7") (pin "3") (pinfunction "CMD_3") (pintype "passive"))
      (node (ref "U$3") (pin "7") (pinfunction "7/RX3_7") (pintype "bidirectional"))
    )
    (net (code "23") (name "NEO_PIX1") (class "Default")
      (node (ref "LED1") (pin "4-DIN") (pinfunction "DI_4-DIN") (pintype "input"))
      (node (ref "U$3") (pin "5") (pinfunction "5/PWM_5") (pintype "bidirectional"))
    )
    (net (code "24") (name "NEO_PIX1_OUT") (class "Default")
      (node (ref "LED16") (pin "2-DOUT") (pinfunction "DO_2-DOUT") (pintype "output"))
      (node (ref "LED17") (pin "4-DIN") (pinfunction "DI_4-DIN") (pintype "input"))
    )
    (net (code "25") (name "Net-(LED1-DO)") (class "Default")
      (node (ref "LED1") (pin "2-DOUT") (pinfunction "DO_2-DOUT") (pintype "output"))
      (node (ref "LED2") (pin "4-DIN") (pinfunction "DI_4-DIN") (pintype "input"))
    )
    (net (code "26") (name "Net-(LED2-DO)") (class "Default")
      (node (ref "LED2") (pin "2-DOUT") (pinfunction "DO_2-DOUT") (pintype "output"))
      (node (ref "LED3") (pin "4-DIN") (pinfunction "DI_4-DIN") (pintype "input"))
    )
    (net (code "27") (name "Net-(LED3-DO)") (class "Default")
      (node (ref "LED3") (pin "2-DOUT") (pinfunction "DO_2-DOUT") (pintype "output"))
      (node (ref "LED4") (pin "4-DIN") (pinfunction "DI_4-DIN") (pintype "input"))
    )
    (net (code "28") (name "Net-(LED4-DO)") (class "Default")
      (node (ref "LED4") (pin "2-DOUT") (pinfunction "DO_2-DOUT") (pintype "output"))
      (node (ref "LED5") (pin "4-DIN") (pinfunction "DI_4-DIN") (pintype "input"))
    )
    (net (code "29") (name "Net-(LED5-DO)") (class "Default")
      (node (ref "LED5") (pin "2-DOUT") (pinfunction "DO_2-DOUT") (pintype "output"))
      (node (ref "LED6") (pin "4-DIN") (pinfunction "DI_4-DIN") (pintype "input"))
    )
    (net (code "30") (name "Net-(LED6-DO)") (class "Default")
      (node (ref "LED6") (pin "2-DOUT") (pinfunction "DO_2-DOUT") (pintype "output"))
      (node (ref "LED7") (pin "4-DIN") (pinfunction "DI_4-DIN") (pintype "input"))
    )
    (net (code "31") (name "Net-(LED7-DO)") (class "Default")
      (node (ref "LED7") (pin "2-DOUT") (pinfunction "DO_2-DOUT") (pintype "output"))
      (node (ref "LED8") (pin "4-DIN") (pinfunction "DI_4-DIN") (pintype "input"))
    )
    (net (code "32") (name "Net-(LED8-DO)") (class "Default")
      (node (ref "LED8") (pin "2-DOUT") (pinfunction "DO_2-DOUT") (pintype "output"))
      (node (ref "LED9") (pin "4-DIN") (pinfunction "DI_4-DIN") (pintype "input"))
    )
    (net (code "33") (name "Net-(LED10-DI)") (class "Default")
      (node (ref "LED10") (pin "4-DIN") (pinfunction "DI_4-DIN") (pintype "input"))
      (node (ref "LED9") (pin "2-DOUT") (pinfunction "DO_2-DOUT") (pintype "output"))
    )
    (net (code "34") (name "Net-(LED10-DO)") (class "Default")
      (node (ref "LED10") (pin "2-DOUT") (pinfunction "DO_2-DOUT") (pintype "output"))
      (node (ref "LED11") (pin "4-DIN") (pinfunction "DI_4-DIN") (pintype "input"))
    )
    (net (code "35") (name "Net-(LED11-DO)") (class "Default")
      (node (ref "LED11") (pin "2-DOUT") (pinfunction "DO_2-DOUT") (pintype "output"))
      (node (ref "LED12") (pin "4-DIN") (pinfunction "DI_4-DIN") (pintype "input"))
    )
    (net (code "36") (name "Net-(LED12-DO)") (class "Default")
      (node (ref "LED12") (pin "2-DOUT") (pinfunction "DO_2-DOUT") (pintype "output"))
      (node (ref "LED13") (pin "4-DIN") (pinfunction "DI_4-DIN") (pintype "input"))
    )
    (net (code "37") (name "Net-(LED13-DO)") (class "Default")
      (node (ref "LED13") (pin "2-DOUT") (pinfunction "DO_2-DOUT") (pintype "output"))
      (node (ref "LED14") (pin "4-DIN") (pinfunction "DI_4-DIN") (pintype "input"))
    )
    (net (code "38") (name "Net-(LED14-DO)") (class "Default")
      (node (ref "LED14") (pin "2-DOUT") (pinfunction "DO_2-DOUT") (pintype "output"))
      (node (ref "LED15") (pin "4-DIN") (pinfunction "DI_4-DIN") (pintype "input"))
    )
    (net (code "39") (name "Net-(LED15-DO)") (class "Default")
      (node (ref "LED15") (pin "2-DOUT") (pinfunction "DO_2-DOUT") (pintype "output"))
      (node (ref "LED16") (pin "4-DIN") (pinfunction "DI_4-DIN") (pintype "input"))
    )
    (net (code "40") (name "Net-(LED17-DO)") (class "Default")
      (node (ref "LED17") (pin "2-DOUT") (pinfunction "DO_2-DOUT") (pintype "output"))
      (node (ref "LED18") (pin "4-DIN") (pinfunction "DI_4-DIN") (pintype "input"))
    )
    (net (code "41") (name "Net-(LED18-DO)") (class "Default")
      (node (ref "LED18") (pin "2-DOUT") (pinfunction "DO_2-DOUT") (pintype "output"))
      (node (ref "LED19") (pin "4-DIN") (pinfunction "DI_4-DIN") (pintype "input"))
    )
    (net (code "42") (name "Net-(LED19-DO)") (class "Default")
      (node (ref "LED19") (pin "2-DOUT") (pinfunction "DO_2-DOUT") (pintype "output"))
      (node (ref "LED20") (pin "4-DIN") (pinfunction "DI_4-DIN") (pintype "input"))
    )
    (net (code "43") (name "Net-(MEMS_FRONT_EX-SD)") (class "Default")
      (node (ref "MEMS_FRONT_EX") (pin "7") (pinfunction "SD_7") (pintype "output"))
      (node (ref "MEMS_FRONT_STD") (pin "6") (pinfunction "DATA_OUT_6") (pintype "output"))
      (node (ref "R14") (pin "1") (pinfunction "1_1") (pintype "passive"))
    )
    (net (code "44") (name "Net-(U$5-PadP$10)") (class "Default")
      (node (ref "U$5") (pin "P$10") (pinfunction "P$10_P$10") (pintype "bidirectional"))
      (node (ref "U$5") (pin "P$11") (pinfunction "P$11_P$11") (pintype "bidirectional"))
      (node (ref "U$5") (pin "P$12") (pinfunction "P$12_P$12") (pintype "bidirectional"))
      (node (ref "U$5") (pin "P$4") (pinfunction "P$4_P$4") (pintype "bidirectional"))
      (node (ref "U$5") (pin "P$5") (pinfunction "P$5_P$5") (pintype "bidirectional"))
      (node (ref "U$5") (pin "P$6") (pinfunction "P$6_P$6") (pintype "bidirectional"))
    )
    (net (code "45") (name "Net-(U$7-OUT_L+)") (class "Default")
      (node (ref "FRONT_OUT") (pin "1") (pinfunction "1_1") (pintype "passive"))
      (node (ref "U$7") (pin "LOUT_H") (pinfunction "OUT_L+_LOUT_H") (pintype "bidirectional"))
    )
    (net (code "46") (name "Net-(U$7-OUT_L-)") (class "Default")
      (node (ref "FRONT_OUT") (pin "2") (pinfunction "2_2") (pintype "passive"))
      (node (ref "U$7") (pin "LOUT_G") (pinfunction "OUT_L-_LOUT_G") (pintype "bidirectional"))
    )
    (net (code "47") (name "Net-(U$7-OUT_R+)") (class "Default")
      (node (ref "REAR_OUT") (pin "1") (pinfunction "1_1") (pintype "passive"))
      (node (ref "U$7") (pin "ROUT_H") (pinfunction "OUT_R+_ROUT_H") (pintype "bidirectional"))
    )
    (net (code "48") (name "Net-(U$7-OUT_R-)") (class "Default")
      (node (ref "REAR_OUT") (pin "2") (pinfunction "2_2") (pintype "passive"))
      (node (ref "U$7") (pin "ROUT_G") (pinfunction "OUT_R-_ROUT_G") (pintype "bidirectional"))
    )
    (net (code "49") (name "Net-(U3-VIN)") (class "Default")
      (node (ref "R10") (pin "2") (pinfunction "2_2") (pintype "passive"))
      (node (ref "U3") (pin "1") (pinfunction "VIN_1") (pintype "input"))
    )
    (net (code "50") (name "Net-(VMEL_FRONT-VDD)") (class "Default")
      (node (ref "C10") (pin "1") (pinfunction "1_1") (pintype "passive"))
      (node (ref "C8") (pin "1") (pinfunction "1_1") (pintype "passive"))
      (node (ref "R1") (pin "1") (pinfunction "1_1") (pintype "passive"))
      (node (ref "VMEL_FRONT") (pin "6") (pinfunction "VDD_6") (pintype "power_in"))
    )
    (net (code "51") (name "Net-(VMEL_REAR-ADDR)") (class "Default")
      (node (ref "C42") (pin "1") (pinfunction "1_1") (pintype "passive"))
      (node (ref "C43") (pin "1") (pinfunction "1_1") (pintype "passive"))
      (node (ref "R2") (pin "1") (pinfunction "1_1") (pintype "passive"))
      (node (ref "VMEL_REAR") (pin "4") (pinfunction "ADDR_4") (pintype "bidirectional"))
      (node (ref "VMEL_REAR") (pin "6") (pinfunction "VDD_6") (pintype "power_in"))
    )
    (net (code "52") (name "ONT") (class "Default")
      (node (ref "C37") (pin "1") (pinfunction "1_1") (pintype "passive"))
      (node (ref "U3") (pin "3") (pinfunction "ONT_3") (pintype "input"))
    )
    (net (code "53") (name "PDT") (class "Default")
      (node (ref "C2") (pin "1") (pinfunction "1_1") (pintype "passive"))
      (node (ref "U3") (pin "7") (pinfunction "PDT_7") (pintype "input"))
    )
    (net (code "54") (name "POT1") (class "Default")
      (node (ref "U$3") (pin "17/A3") (pinfunction "17/A3/T_17/A3") (pintype "bidirectional"))
      (node (ref "U$4") (pin "P$1") (pinfunction "P$1_P$1") (pintype "bidirectional"))
    )
    (net (code "55") (name "POT2") (class "Default")
      (node (ref "U$3") (pin "21/A7") (pinfunction "21/A7/PWM_21/A7") (pintype "bidirectional"))
      (node (ref "U$6") (pin "P$1") (pinfunction "P$1_P$1") (pintype "bidirectional"))
    )
    (net (code "56") (name "PWR_INT") (class "Default")
      (node (ref "R8") (pin "1") (pinfunction "1_1") (pintype "passive"))
      (node (ref "U$3") (pin "15/A1") (pinfunction "15/A1/T_15/A1") (pintype "bidirectional"))
      (node (ref "U3") (pin "5") (pinfunction "*INT_5") (pintype "output"))
    )
    (net (code "57") (name "PWR_KILL") (class "Default")
      (node (ref "U$3") (pin "8") (pinfunction "8/TX3_8") (pintype "bidirectional"))
      (node (ref "U3") (pin "8") (pinfunction "*KILL_8") (pintype "input"))
    )
    (net (code "58") (name "REAR_PRE_R") (class "Default")
      (node (ref "MEMS_REAR_EX") (pin "7") (pinfunction "SD_7") (pintype "output"))
      (node (ref "MEMS_REAR_STD") (pin "6") (pinfunction "DATA_OUT_6") (pintype "output"))
      (node (ref "R16") (pin "1") (pinfunction "1_1") (pintype "passive"))
    )
    (net (code "59") (name "SCL") (class "Default")
      (node (ref "R4") (pin "1") (pinfunction "1_1") (pintype "passive"))
      (node (ref "U$3") (pin "19/A5") (pinfunction "19/A5/T/SCL0_19/A5") (pintype "bidirectional"))
      (node (ref "U1") (pin "2") (pinfunction "SCL/SPC_2") (pintype "bidirectional"))
      (node (ref "U2") (pin "2") (pinfunction "SCL_2") (pintype "bidirectional"))
      (node (ref "VMEL_FRONT") (pin "5") (pinfunction "SCL_5") (pintype "input"))
      (node (ref "VMEL_REAR") (pin "5") (pinfunction "SCL_5") (pintype "input"))
    )
    (net (code "60") (name "SDA") (class "Default")
      (node (ref "R3") (pin "1") (pinfunction "1_1") (pintype "passive"))
      (node (ref "U$3") (pin "18/A4") (pinfunction "18/A4/T/SDA0_18/A4") (pintype "bidirectional"))
      (node (ref "U1") (pin "3") (pinfunction "SDA/SDI_3") (pintype "input"))
      (node (ref "U2") (pin "3") (pinfunction "SDA_3") (pintype "bidirectional"))
      (node (ref "VMEL_FRONT") (pin "2") (pinfunction "SDA_2") (pintype "bidirectional"))
      (node (ref "VMEL_REAR") (pin "2") (pinfunction "SDA_2") (pintype "bidirectional"))
    )
    (net (code "61") (name "SD_CS") (class "Default")
      (node (ref "J7") (pin "2") (pinfunction "CD/DAT3_2") (pintype "passive"))
      (node (ref "R11") (pin "1") (pinfunction "1_1") (pintype "passive"))
      (node (ref "U$3") (pin "10") (pinfunction "10/TX2/PWM_10") (pintype "bidirectional"))
    )
    (net (code "62") (name "SPI_CLK") (class "Default")
      (node (ref "J7") (pin "5") (pinfunction "CLK_5") (pintype "passive"))
      (node (ref "U$3") (pin "14/A0") (pinfunction "14/A1_14/A0") (pintype "bidirectional"))
    )
    (net (code "63") (name "VEML_INT_1") (class "Default")
      (node (ref "VMEL_FRONT") (pin "3") (pinfunction "INT_3") (pintype "output"))
    )
    (net (code "64") (name "VEML_INT_2") (class "Default")
      (node (ref "VMEL_REAR") (pin "3") (pinfunction "INT_3") (pintype "output"))
    )
    (net (code "65") (name "_BCLK") (class "Default")
      (node (ref "R5") (pin "2") (pinfunction "2_2") (pintype "passive"))
      (node (ref "U$3") (pin "9") (pinfunction "9/RX2/PWM_9") (pintype "bidirectional"))
    )
    (net (code "66") (name "_LRCLK") (class "Default")
      (node (ref "R7") (pin "2") (pinfunction "2_2") (pintype "passive"))
      (node (ref "U$3") (pin "23/A9") (pinfunction "23/A9/T/PWM_23/A9") (pintype "bidirectional"))
    )
    (net (code "67") (name "unconnected-(J7-CD_SW-Pad9)") (class "Default")
      (node (ref "J7") (pin "9") (pinfunction "CD_SW_9") (pintype "passive"))
    )
    (net (code "68") (name "unconnected-(J7-DAT1-Pad8)") (class "Default")
      (node (ref "J7") (pin "8") (pinfunction "DAT1_8") (pintype "passive"))
    )
    (net (code "69") (name "unconnected-(J7-DAT2-Pad1)") (class "Default")
      (node (ref "J7") (pin "1") (pinfunction "DAT2_1") (pintype "passive"))
    )
    (net (code "70") (name "unconnected-(LED20-DO-Pad2-DOUT)") (class "Default")
      (node (ref "LED20") (pin "2-DOUT") (pinfunction "DO_2-DOUT") (pintype "output"))
    )
    (net (code "71") (name "unconnected-(PWR-PadP$2)") (class "Default")
      (node (ref "PWR") (pin "P$2") (pinfunction "P$2_P$2") (pintype "bidirectional"))
    )
    (net (code "72") (name "unconnected-(U$7-IN_GND-PadIN_G)") (class "Default")
      (node (ref "U$7") (pin "IN_G") (pinfunction "IN_GND_IN_G") (pintype "bidirectional"))
    )
    (net (code "73") (name "unconnected-(U$7-PadIN_L)") (class "Default")
      (node (ref "U$7") (pin "IN_L") (pinfunction "IN_L_IN_L") (pintype "bidirectional"))
    )
    (net (code "74") (name "unconnected-(U$7-PadIN_R)") (class "Default")
      (node (ref "U$7") (pin "IN_R") (pinfunction "IN_R_IN_R") (pintype "bidirectional"))
    )
    (net (code "75") (name "unconnected-(U1-REGOUT-Pad14)") (class "Default")
      (node (ref "U1") (pin "14") (pinfunction "REGOUT_14") (pintype "passive"))
    )
    (net (code "76") (name "unconnected-(U1-RESV7-Pad7)") (class "Default")
      (node (ref "U1") (pin "7") (pinfunction "RESV7_7") (pintype "passive"))
    )
  )
)
